# design.net
KiCad netlist of a schematic drawn in Altium Designer
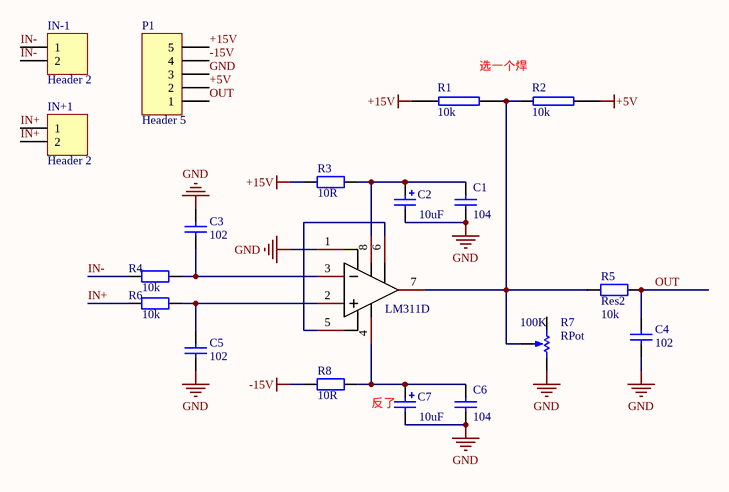
[diagram p0: 电压过零比较器.SchDoc]

(export (version "E")
  (design (tool "Eeschema 10.0.6"))
  (components
    (comp (ref "C1")
      (value "104")
      (footprint "0805")
      (description "电容0805")
      (fields (field (name "Comment") "Cap") (field (name "PUBLISHER") "Altium Limited"))
      (libsource (lib "Miscellaneous Devices") (part "Cap"))
    )
    (comp (ref "C2")
      (value "10uF")
      (footprint "1210")
      (description "Polarized Capacitor (Axial) 1210")
      (fields (field (name "Comment") "Cap Pol2") (field (name "PUBLISHER") "Altium Limited"))
      (libsource (lib "Miscellaneous Devices") (part "Cap Pol2"))
    )
    (comp (ref "C3")
      (value "102")
      (footprint "0805")
      (description "电容0805")
      (fields (field (name "Comment") "Cap") (field (name "PUBLISHER") "Altium Limited"))
      (libsource (lib "Miscellaneous Devices") (part "Cap"))
    )
    (comp (ref "C4")
      (value "102")
      (footprint "0805")
      (description "电容0805")
      (fields (field (name "Comment") "Cap") (field (name "PUBLISHER") "Altium Limited"))
      (libsource (lib "Miscellaneous Devices") (part "Cap"))
    )
    (comp (ref "C5")
      (value "102")
      (footprint "0805")
      (description "电容0805")
      (fields (field (name "Comment") "Cap") (field (name "PUBLISHER") "Altium Limited"))
      (libsource (lib "Miscellaneous Devices") (part "Cap"))
    )
    (comp (ref "C6")
      (value "104")
      (footprint "0805")
      (description "电容0805")
      (fields (field (name "Comment") "Cap") (field (name "PUBLISHER") "Altium Limited"))
      (libsource (lib "Miscellaneous Devices") (part "Cap"))
    )
    (comp (ref "C7")
      (value "10uF")
      (footprint "1210")
      (description "Polarized Capacitor (Axial) 1210")
      (fields (field (name "Comment") "Cap Pol2") (field (name "PUBLISHER") "Altium Limited"))
      (libsource (lib "Miscellaneous Devices") (part "Cap Pol2"))
    )
    (comp (ref "IN+1")
      (value "Header 2")
      (footprint "POWER_2PIN 1")
      (description "Header, 2-Pin")
      (fields (field (name "PUBLISHER") "Altium Limited"))
      (libsource (lib "Miscellaneous Connectors") (part "Header 2"))
    )
    (comp (ref "IN-1")
      (value "Header 2")
      (footprint "POWER_2PIN 1")
      (description "Header, 2-Pin")
      (fields (field (name "PUBLISHER") "Altium Limited"))
      (libsource (lib "Miscellaneous Connectors") (part "Header 2"))
    )
    (comp (ref "P1")
      (value "Header 5")
      (footprint "POWER_5PIN")
      (description "Header, 5-Pin")
      (fields (field (name "PUBLISHER") "Altium Limited"))
      (libsource (lib "Miscellaneous Connectors") (part "Header 5"))
    )
    (comp (ref "R1")
      (value "10k")
      (footprint "AXIAL-0.4")
      (description "电阻")
      (libsource (lib "采集下板") (part "RES2"))
    )
    (comp (ref "R2")
      (value "10k")
      (footprint "AXIAL-0.4")
      (description "电阻")
      (libsource (lib "采集下板") (part "RES2"))
    )
    (comp (ref "R3")
      (value "10R")
      (footprint "0805")
      (description "电阻")
      (fields (field (name "Comment") "Res2") (field (name "PUBLISHER") "Altium Limited"))
      (libsource (lib "Miscellaneous Devices") (part "Res2"))
    )
    (comp (ref "R4")
      (value "10k")
      (footprint "0805")
      (description "电阻")
      (fields (field (name "Comment") "Res2") (field (name "PUBLISHER") "Altium Limited"))
      (libsource (lib "Miscellaneous Devices") (part "Res2"))
    )
    (comp (ref "R5")
      (value "Res2")
      (footprint "0805")
      (description "Resistor")
      (fields (field (name "ALTIUM_VALUE") "10k") (field (name "PUBLISHER") "Altium Limited"))
      (libsource (lib "") (part "Res2_1"))
    )
    (comp (ref "R6")
      (value "10k")
      (footprint "0805")
      (description "电阻")
      (fields (field (name "Comment") "Res2") (field (name "PUBLISHER") "Altium Limited"))
      (libsource (lib "Miscellaneous Devices") (part "Res2"))
    )
    (comp (ref "R7")
      (value "RPot")
      (footprint "VR5")
      (description "Potentiometer")
      (fields (field (name "ALTIUM_VALUE") "100K") (field (name "PUBLISHER") "Altium Limited"))
      (libsource (lib "Miscellaneous Devices") (part "RPot"))
    )
    (comp (ref "R8")
      (value "10R")
      (footprint "0805")
      (description "电阻")
      (fields (field (name "Comment") "Res2") (field (name "PUBLISHER") "Altium Limited"))
      (libsource (lib "Miscellaneous Devices") (part "Res2"))
    )
    (comp (ref "U1") (value "LM311D") (footprint "SO8") (libsource (lib "SchLib_ABB") (part "LM311D")))
  )
  (nets
    (net (code "1") (name "+5V") (class "Default")
      (node (ref "P1") (pin "2") (pinfunction "2_2") (pintype "passive"))
      (node (ref "R2") (pin "2") (pinfunction "2_2") (pintype "passive"))
    )
    (net (code "2") (name "+15V") (class "Default")
      (node (ref "P1") (pin "5") (pinfunction "5_5") (pintype "passive"))
      (node (ref "R1") (pin "1") (pinfunction "1_1") (pintype "passive"))
      (node (ref "R3") (pin "2") (pinfunction "2_2") (pintype "passive"))
    )
    (net (code "3") (name "-15V") (class "Default")
      (node (ref "P1") (pin "4") (pinfunction "4_4") (pintype "passive"))
      (node (ref "R8") (pin "2") (pinfunction "2_2") (pintype "passive"))
    )
    (net (code "4") (name "/IN+") (class "Default")
      (node (ref "IN+1") (pin "1") (pinfunction "1_1") (pintype "passive"))
      (node (ref "IN+1") (pin "2") (pinfunction "2_2") (pintype "passive"))
      (node (ref "R6") (pin "2") (pinfunction "2_2") (pintype "passive"))
    )
    (net (code "5") (name "/IN-") (class "Default")
      (node (ref "IN-1") (pin "1") (pinfunction "1_1") (pintype "passive"))
      (node (ref "IN-1") (pin "2") (pinfunction "2_2") (pintype "passive"))
      (node (ref "R4") (pin "2") (pinfunction "2_2") (pintype "passive"))
    )
    (net (code "6") (name "/OUT") (class "Default")
      (node (ref "C4") (pin "2") (pinfunction "2_2") (pintype "passive"))
      (node (ref "P1") (pin "1") (pinfunction "1_1") (pintype "passive"))
      (node (ref "R5") (pin "2") (pinfunction "2_2") (pintype "passive"))
    )
    (net (code "7") (name "GND") (class "Default")
      (node (ref "C1") (pin "1") (pinfunction "1_1") (pintype "passive"))
      (node (ref "C2") (pin "2") (pinfunction "2_2") (pintype "passive"))
      (node (ref "C3") (pin "2") (pinfunction "2_2") (pintype "passive"))
      (node (ref "C4") (pin "1") (pinfunction "1_1") (pintype "passive"))
      (node (ref "C5") (pin "1") (pinfunction "1_1") (pintype "passive"))
      (node (ref "C6") (pin "1") (pinfunction "1_1") (pintype "passive"))
      (node (ref "C7") (pin "2") (pinfunction "2_2") (pintype "passive"))
      (node (ref "P1") (pin "3") (pinfunction "3_3") (pintype "passive"))
      (node (ref "R7") (pin "3") (pinfunction "BOT_3") (pintype "passive"))
      (node (ref "U1") (pin "1") (pinfunction "GROUND_1") (pintype "passive"))
    )
    (net (code "8") (name "Net-(R7-TAP)") (class "Default")
      (node (ref "R1") (pin "2") (pinfunction "2_2") (pintype "passive"))
      (node (ref "R2") (pin "1") (pinfunction "1_1") (pintype "passive"))
      (node (ref "R5") (pin "1") (pinfunction "1_1") (pintype "passive"))
      (node (ref "R7") (pin "2") (pinfunction "TAP_2") (pintype "passive"))
      (node (ref "U1") (pin "7") (pinfunction "OUT_7") (pintype "passive"))
    )
    (net (code "9") (name "Net-(U1-BALANCE)") (class "Default")
      (node (ref "U1") (pin "5") (pinfunction "BALANCE_5") (pintype "passive"))
      (node (ref "U1") (pin "6") (pinfunction "STROBE/BALANCE_6") (pintype "passive"))
    )
    (net (code "10") (name "Net-(U1-IN+)") (class "Default")
      (node (ref "C5") (pin "2") (pinfunction "2_2") (pintype "passive"))
      (node (ref "R6") (pin "1") (pinfunction "1_1") (pintype "passive"))
      (node (ref "U1") (pin "2") (pinfunction "IN+_2") (pintype "passive"))
    )
    (net (code "11") (name "Net-(U1-IN-)") (class "Default")
      (node (ref "C3") (pin "1") (pinfunction "1_1") (pintype "passive"))
      (node (ref "R4") (pin "1") (pinfunction "1_1") (pintype "passive"))
      (node (ref "U1") (pin "3") (pinfunction "IN-_3") (pintype "passive"))
    )
    (net (code "12") (name "Net-(U1-V+)") (class "Default")
      (node (ref "C1") (pin "2") (pinfunction "2_2") (pintype "passive"))
      (node (ref "C2") (pin "1") (pinfunction "1_1") (pintype "passive"))
      (node (ref "R3") (pin "1") (pinfunction "1_1") (pintype "passive"))
      (node (ref "U1") (pin "8") (pinfunction "V+_8") (pintype "passive"))
    )
    (net (code "13") (name "Net-(U1-VCC-)") (class "Default")
      (node (ref "C6") (pin "2") (pinfunction "2_2") (pintype "passive"))
      (node (ref "C7") (pin "1") (pinfunction "1_1") (pintype "passive"))
      (node (ref "R8") (pin "1") (pinfunction "1_1") (pintype "passive"))
      (node (ref "U1") (pin "4") (pinfunction "VCC-_4") (pintype "passive"))
    )
    (net (code "14") (name "unconnected-(R7-TOP-Pad1)") (class "Default")
      (node (ref "R7") (pin "1") (pinfunction "TOP_1") (pintype "passive"))
    )
  )
)
